# Main.net
KiCad netlist of a schematic drawn in Altium Designer
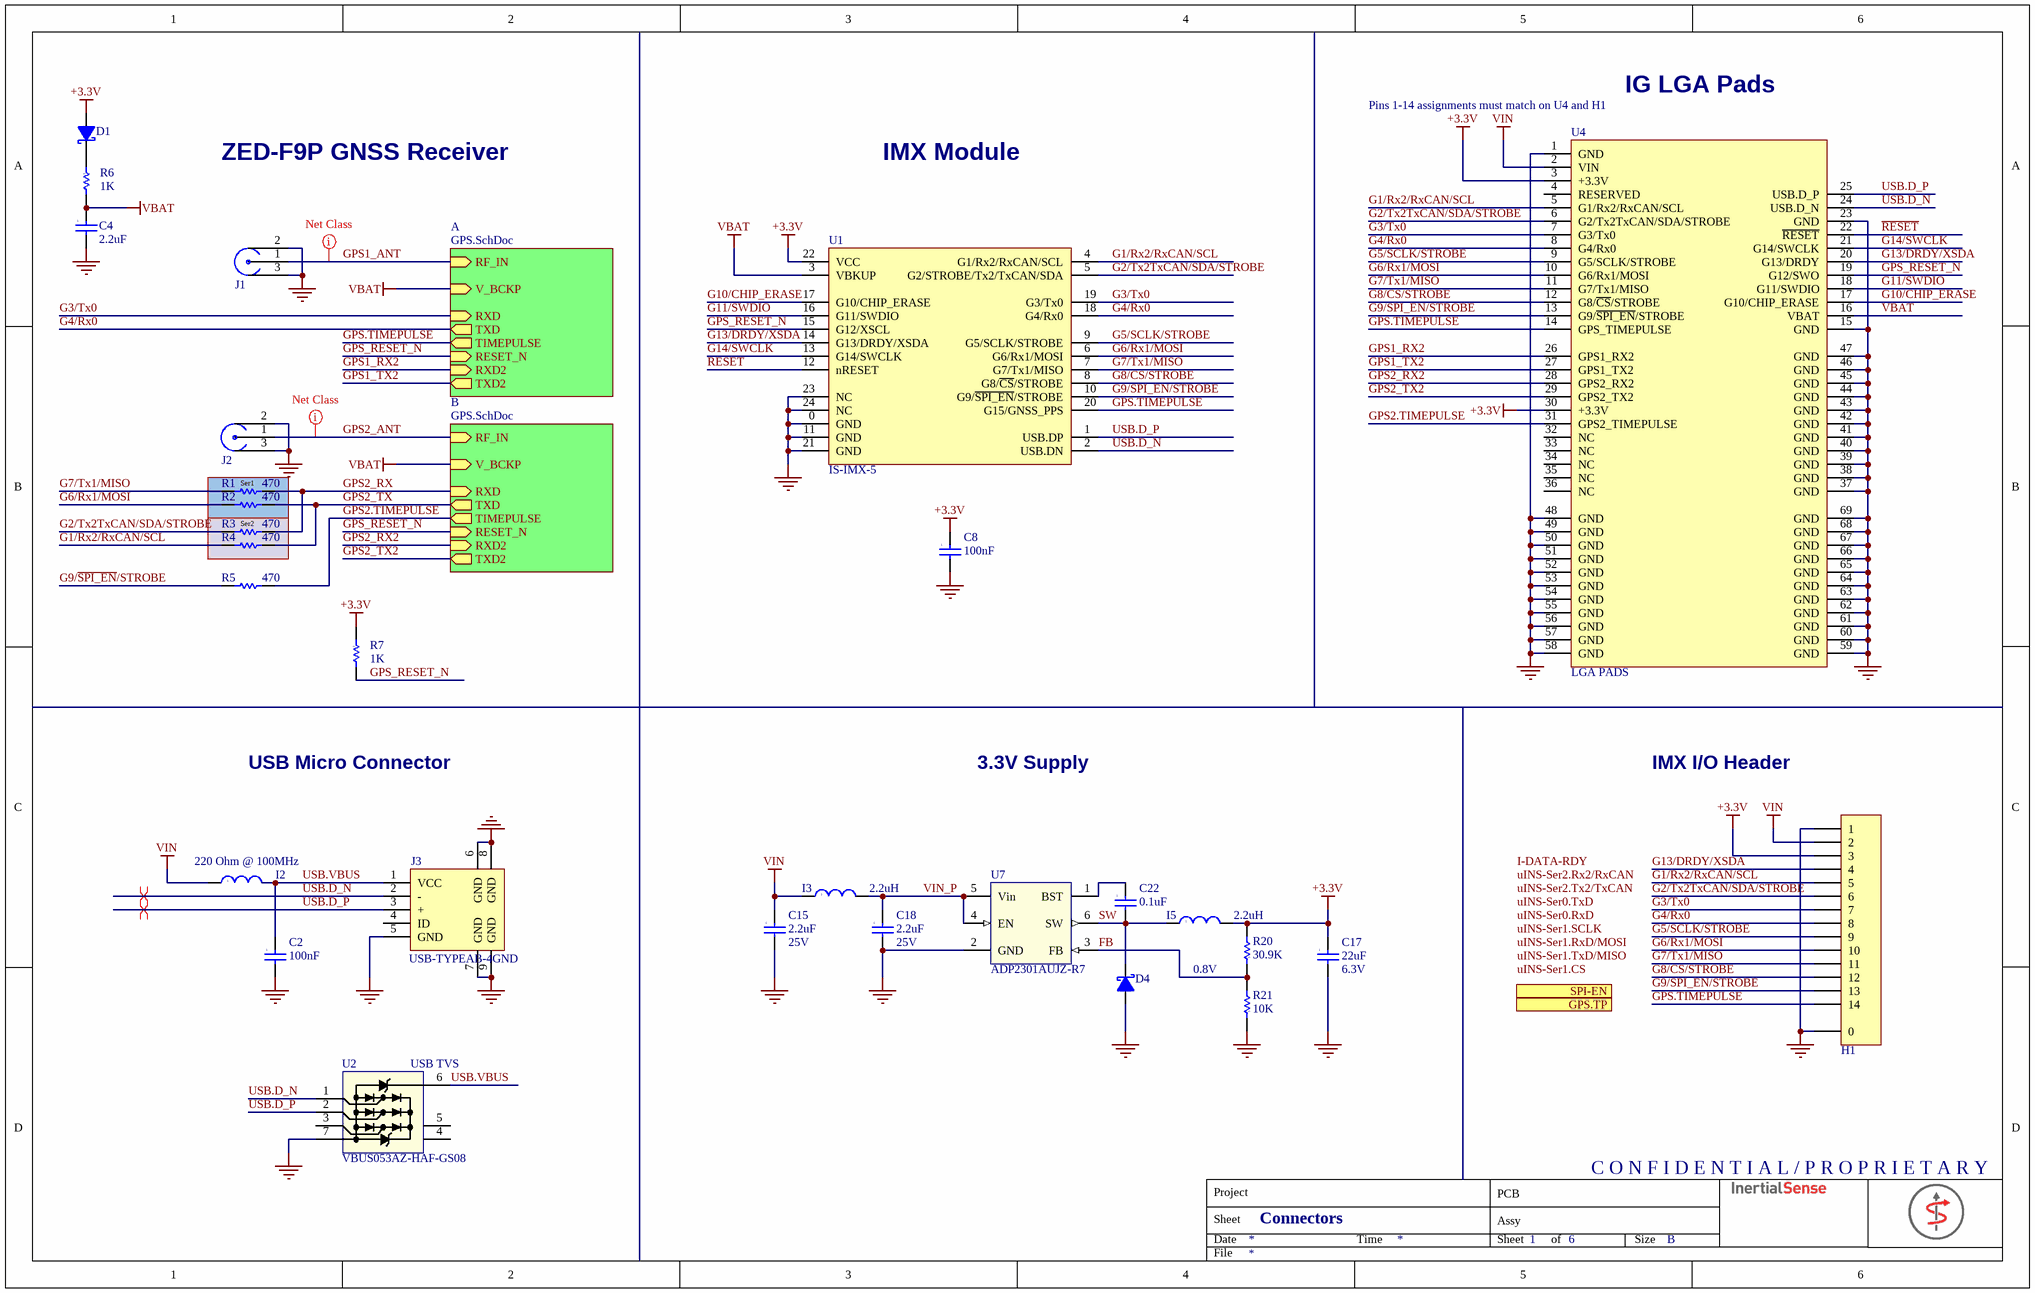
[diagram p0: Main.SchDoc]

(export (version "E")
  (design (tool "Eeschema 10.0.6"))
  (components
    (comp (ref "C2")
      (value "100nF")
      (footprint "0402")
      (description "CAP CER .10UF 50V X7R 10% 0402")
      (fields
        (field (name "MANUFACTURER") "TDK Corporation")
        (field (name "MANUFACTURER PART NUMBER") "C1005X7R1H104K")
        (field (name "PUBLISHER") "Altium Limited")
      )
      (libsource (lib "") (part "Cap_1"))
    )
    (comp (ref "C4")
      (value "2.2uF")
      (footprint "0402")
      (description "0402 2.2 uF 6.3 V ±10% Tolerance X6S Multilayer Ceramic Capacitor")
      (fields
        (field (name "MANUFACTURER") "Murata")
        (field (name "MANUFACTURER PART NUMBER") "GRM155C80J225KE95D")
        (field (name "PUBLISHER") "Altium Limited")
      )
      (libsource (lib "General") (part "Cap"))
    )
    (comp (ref "C8")
      (value "100nF")
      (footprint "0402")
      (description "CAP CER .10UF 50V X7R 10% 0402")
      (fields
        (field (name "MANUFACTURER") "TDK Corporation")
        (field (name "MANUFACTURER PART NUMBER") "C1005X7R1H104K")
        (field (name "PUBLISHER") "Altium Limited")
      )
      (libsource (lib "") (part "Cap_1"))
    )
    (comp (ref "C15")
      (value "2.2uF")
      (footprint "0603")
      (description "CAP CER 2.2UF 25V X6S 0603")
      (fields
        (field (name "MANUFACTURER") "Murata")
        (field (name "MANUFACTURER PART NUMBER") "GRT188C81E225KE13D")
        (field (name "VOLTAGE RATING") "25V")
        (field (name "PUBLISHER") "Altium Limited")
      )
      (libsource (lib "General") (part "Cap"))
    )
    (comp (ref "C17")
      (value "22uF")
      (footprint "0603")
      (description "CAP CER 22UF 6.3V X6S 0603")
      (fields
        (field (name "MANUFACTURER") "Murata")
        (field (name "MANUFACTURER PART NUMBER") "GRM188C80J226ME15D")
        (field (name "VOLTAGE RATING") "6.3V")
        (field (name "PUBLISHER") "Altium Limited")
      )
      (libsource (lib "General") (part "Cap"))
    )
    (comp (ref "C18")
      (value "2.2uF")
      (footprint "0603")
      (description "CAP CER 2.2UF 25V X6S 0603")
      (fields
        (field (name "MANUFACTURER") "Murata")
        (field (name "MANUFACTURER PART NUMBER") "GRT188C81E225KE13D")
        (field (name "VOLTAGE RATING") "25V")
        (field (name "PUBLISHER") "Altium Limited")
      )
      (libsource (lib "General") (part "Cap"))
    )
    (comp (ref "C22")
      (value "0.1uF")
      (footprint "0402")
      (description "CAP CER 0.1UF 50V X7R 0402")
      (fields
        (field (name "MANUFACTURER") "TDK")
        (field (name "MANUFACTURER PART NUMBER") "CGA2B3X7R1H104K050BB")
        (field (name "PUBLISHER") "Altium Limited")
      )
      (libsource (lib "General") (part "Cap"))
    )
    (comp (ref "D1")
      (value "Diode - Schottky")
      (footprint "D0603B")
      (description "DIODE SCHOTTKY 30V 2A 0603")
      (fields
        (field (name "MANUFACTURER") "Vishay")
        (field (name "MANUFACTURER PART NUMBER") "VSKY20301608-G4-08")
      )
      (libsource (lib "General") (part "Diode - Schottky"))
    )
    (comp (ref "D4")
      (value "Diode - Schottky")
      (footprint "D0603B")
      (description "DIODE SCHOTTKY 30V 2A 0603")
      (fields
        (field (name "MANUFACTURER") "Vishay")
        (field (name "MANUFACTURER PART NUMBER") "VSKY20301608-G4-08")
      )
      (libsource (lib "General") (part "Diode - Schottky"))
    )
    (comp (ref "H1")
      (value "Hdr - 14pin - mount")
      (footprint "SM14B-GHS-TB(LF)(SN)")
      (description "Conn Shrouded Header HDR 14 POS 1.25mm Solder ST Top Entry SMD T/R")
      (fields
        (field (name "MANUFACTURER") "JST")
        (field (name "MANUFACTURER PART NUMBER") "SM14B-GHS-TB(LF)(SN)")
      )
      (libsource (lib "Connectors") (part "Hdr - 14pin - mount"))
    )
    (comp (ref "I2")
      (value "220 Ohm @ 100MHz")
      (footprint "I0603")
      (description "FERRITE CHIP 220 OHM 2500MA 0603")
      (fields
        (field (name "MANUFACTURER") "Murata Electronics North America")
        (field (name "MANUFACTURER PART NUMBER") "BLM18SG221TN1D")
      )
      (libsource (lib "") (part "Inductor_1"))
    )
    (comp (ref "I3")
      (value "2.2uH")
      (footprint "0806")
      (description "FIXED IND 2.2UH 1.2A 110 MOHM")
      (fields
        (field (name "MANUFACTURER") "TDK")
        (field (name "MANUFACTURER PART NUMBER") "MLP2016H2R2MT0S1")
      )
      (libsource (lib "General") (part "Inductor"))
    )
    (comp (ref "I5")
      (value "2.2uH")
      (footprint "0806")
      (description "FIXED IND 2.2UH 1.2A 110 MOHM")
      (fields
        (field (name "MANUFACTURER") "TDK")
        (field (name "MANUFACTURER PART NUMBER") "MLP2016H2R2MT0S1")
      )
      (libsource (lib "General") (part "Inductor"))
    )
    (comp (ref "J1")
      (value "RF - GND x 2")
      (footprint "RF UMC SMD")
      (description "CONN UMC RCPT STR 50 OHM SMD")
      (fields
        (field (name "MANUFACTURER") "Emerson Network Power Connectivity Johnson")
        (field (name "MANUFACTURER PART NUMBER") "128-0711-201")
      )
      (libsource (lib "Connectors") (part "RF - GND x 2"))
    )
    (comp (ref "J2")
      (value "RF - GND x 2")
      (footprint "RF UMC SMD")
      (description "CONN UMC RCPT STR 50 OHM SMD")
      (fields
        (field (name "MANUFACTURER") "Emerson Network Power Connectivity Johnson")
        (field (name "MANUFACTURER PART NUMBER") "128-0711-201")
      )
      (libsource (lib "Connectors") (part "RF - GND x 2"))
    )
    (comp (ref "J3")
      (value "USB-TYPEAB-4GND")
      (footprint "USB Micro AB R/A THR")
      (description "CONN USB AB 4POS")
      (fields
        (field (name "MANUFACTURER") "Amphenol FCI")
        (field (name "MANUFACTURER PART NUMBER") "10118194-0001LF")
      )
      (libsource (lib "Connectors") (part "USB-TYPEAB-4GND"))
    )
    (comp (ref "R1")
      (value "470")
      (footprint "R0402")
      (description "RES 470 OHM 1/16W 1% 0402 SMD")
      (fields
        (field (name "MANUFACTURER") "Vishay Dale")
        (field (name "MANUFACTURER PART NUMBER") "CRCW0402470RFKED")
      )
      (libsource (lib "General") (part "Res"))
    )
    (comp (ref "R2")
      (value "470")
      (footprint "R0402")
      (description "RES 470 OHM 1/16W 1% 0402 SMD")
      (fields
        (field (name "MANUFACTURER") "Vishay Dale")
        (field (name "MANUFACTURER PART NUMBER") "CRCW0402470RFKED")
      )
      (libsource (lib "General") (part "Res"))
    )
    (comp (ref "R3")
      (value "470")
      (footprint "R0402")
      (description "RES 470 OHM 1/16W 1% 0402 SMD")
      (fields
        (field (name "MANUFACTURER") "Vishay Dale")
        (field (name "MANUFACTURER PART NUMBER") "CRCW0402470RFKED")
      )
      (libsource (lib "General") (part "Res"))
    )
    (comp (ref "R4")
      (value "470")
      (footprint "R0402")
      (description "RES 470 OHM 1/16W 1% 0402 SMD")
      (fields
        (field (name "MANUFACTURER") "Vishay Dale")
        (field (name "MANUFACTURER PART NUMBER") "CRCW0402470RFKED")
      )
      (libsource (lib "General") (part "Res"))
    )
    (comp (ref "R5")
      (value "470")
      (footprint "R0402")
      (description "RES 470 OHM 1/16W 1% 0402 SMD")
      (fields
        (field (name "MANUFACTURER") "Vishay Dale")
        (field (name "MANUFACTURER PART NUMBER") "CRCW0402470RFKED")
      )
      (libsource (lib "General") (part "Res"))
    )
    (comp (ref "R6")
      (value "1K")
      (footprint "R0402")
      (description "1 kOhms ±1% 0.063W, 1/16W Chip Resistor 0402 (1005 Metric) Moisture Resistant Thick Film")
      (fields
        (field (name "MANUFACTURER") "Yageo")
        (field (name "MANUFACTURER PART NUMBER") "RC0402FR-071KL")
      )
      (libsource (lib "") (part "Res_1"))
    )
    (comp (ref "R7")
      (value "1K")
      (footprint "R0402")
      (description "1 kOhms ±1% 0.063W, 1/16W Chip Resistor 0402 (1005 Metric) Moisture Resistant Thick Film")
      (fields
        (field (name "MANUFACTURER") "Yageo")
        (field (name "MANUFACTURER PART NUMBER") "RC0402FR-071KL")
      )
      (libsource (lib "") (part "Res_1"))
    )
    (comp (ref "R20")
      (value "30.9K")
      (footprint "R0402")
      (description "RES TF 30.9K OHM 1% 1/16W 0402")
      (fields
        (field (name "MANUFACTURER") "Stackpole Electronics Inc")
        (field (name "MANUFACTURER PART NUMBER") "RMCF0402FT30K9")
      )
      (libsource (lib "") (part "Res_2"))
    )
    (comp (ref "R21")
      (value "10K")
      (footprint "R0402")
      (description "RES 10.0K OHM 1/16W 1% 0402 SMD")
      (fields
        (field (name "MANUFACTURER") "Yageo")
        (field (name "MANUFACTURER PART NUMBER") "RC0402FR-0710KL")
      )
      (libsource (lib "") (part "Res_2"))
    )
    (comp (ref "U1")
      (value "IMX")
      (footprint "IS-IMX-5.0")
      (description "Inertial Sense IMX")
      (fields
        (field (name "MANUFACTURER") "Inertial Sense")
        (field (name "MANUFACTURER PART NUMBER") "IS-IMX-5")
      )
      (libsource (lib "IS-IMX-5") (part "IS-IMX-5.0"))
    )
    (comp (ref "U2")
      (value "VBUS053")
      (footprint "QFN50P160X160X60-6N")
      (description "ESD SUPPRESS 5.5V 36W 3-Line USB")
      (fields
        (field (name "MANUFACTURER") "Vishay Semiconductors")
        (field (name "MANUFACTURER PART NUMBER") "VBUS053AZ-HAF-GS08")
      )
      (libsource (lib "ICs") (part "VBUS053"))
    )
    (comp (ref "U4")
      (value "LGA PADS")
      (footprint "IG-1.2-G2_LGA")
      (description "IMX multi-frequency RTK-GNSS Module")
      (libsource (lib "Sensors") (part "IG_1.2-G2_LGA"))
    )
    (comp (ref "U7")
      (value "ADP2301")
      (footprint "MO-178-AB")
      (description "IC BUCK ADJ 1.2A 6TSOT")
      (fields
        (field (name "MANUFACTURER") "Analog Devices Inc")
        (field (name "MANUFACTURER PART NUMBER") "ADP2301AUJZ-R7")
      )
      (libsource (lib "ICs") (part "ADP2301"))
    )
  )
  (nets
    (net (code "1") (name "+3.3V") (class "Default")
      (node (ref "C17") (pin "1") (pinfunction "1_1") (pintype "passive"))
      (node (ref "C8") (pin "1") (pinfunction "1_1") (pintype "passive"))
      (node (ref "D1") (pin "A") (pinfunction "A_A") (pintype "passive"))
      (node (ref "H1") (pin "3") (pinfunction "3_3") (pintype "passive"))
      (node (ref "I5") (pin "2") (pinfunction "2_2") (pintype "passive"))
      (node (ref "R20") (pin "2") (pinfunction "2_2") (pintype "passive"))
      (node (ref "R7") (pin "1") (pinfunction "1_1") (pintype "passive"))
      (node (ref "U1") (pin "22") (pinfunction "VCC_22") (pintype "power_in"))
      (node (ref "U4") (pin "3") (pinfunction "+3.3V_3") (pintype "passive"))
      (node (ref "U4") (pin "30") (pinfunction "+3.3V_30") (pintype "passive"))
    )
    (net (code "2") (name "/FB") (class "Default")
      (node (ref "R20") (pin "1") (pinfunction "1_1") (pintype "passive"))
      (node (ref "R21") (pin "2") (pinfunction "2_2") (pintype "passive"))
      (node (ref "U7") (pin "3") (pinfunction "FB_3") (pintype "input"))
    )
    (net (code "3") (name "/G1{slash}Rx2{slash}RxCAN{slash}SCL") (class "Default")
      (node (ref "H1") (pin "5") (pinfunction "5_5") (pintype "passive"))
      (node (ref "R4") (pin "1") (pinfunction "1_1") (pintype "passive"))
      (node (ref "U1") (pin "4") (pinfunction "G1/Rx2/RxCAN/SCL_4") (pintype "passive"))
      (node (ref "U4") (pin "5") (pinfunction "G1/Rx2/RxCAN/SCL_5") (pintype "passive"))
    )
    (net (code "4") (name "/G2{slash}Tx2TxCAN{slash}SDA{slash}STROBE") (class "Default")
      (node (ref "H1") (pin "6") (pinfunction "6_6") (pintype "passive"))
      (node (ref "R3") (pin "1") (pinfunction "1_1") (pintype "passive"))
      (node (ref "U1") (pin "5") (pinfunction "G2/STROBE/Tx2/TxCAN/SDA_5") (pintype "passive"))
      (node (ref "U4") (pin "6") (pinfunction "G2/Tx2TxCAN/SDA/STROBE_6") (pintype "passive"))
    )
    (net (code "5") (name "/G3{slash}Tx0") (class "Default")
      (node (ref "H1") (pin "7") (pinfunction "7_7") (pintype "passive"))
      (node (ref "U1") (pin "19") (pinfunction "G3/Tx0_19") (pintype "passive"))
      (node (ref "U4") (pin "7") (pinfunction "G3/Tx0_7") (pintype "passive"))
    )
    (net (code "6") (name "/G4{slash}Rx0") (class "Default")
      (node (ref "H1") (pin "8") (pinfunction "8_8") (pintype "passive"))
      (node (ref "U1") (pin "18") (pinfunction "G4/Rx0_18") (pintype "passive"))
      (node (ref "U4") (pin "8") (pinfunction "G4/Rx0_8") (pintype "passive"))
    )
    (net (code "7") (name "/G5{slash}SCLK{slash}STROBE") (class "Default")
      (node (ref "H1") (pin "9") (pinfunction "9_9") (pintype "passive"))
      (node (ref "U1") (pin "9") (pinfunction "G5/SCLK/STROBE_9") (pintype "passive"))
      (node (ref "U4") (pin "9") (pinfunction "G5/SCLK/STROBE_9") (pintype "passive"))
    )
    (net (code "8") (name "/G6{slash}Rx1{slash}MOSI") (class "Default")
      (node (ref "H1") (pin "10") (pinfunction "10_10") (pintype "passive"))
      (node (ref "R2") (pin "1") (pinfunction "1_1") (pintype "passive"))
      (node (ref "U1") (pin "6") (pinfunction "G6/Rx1/MOSI_6") (pintype "passive"))
      (node (ref "U4") (pin "10") (pinfunction "G6/Rx1/MOSI_10") (pintype "passive"))
    )
    (net (code "9") (name "/G7{slash}Tx1{slash}MISO") (class "Default")
      (node (ref "H1") (pin "11") (pinfunction "11_11") (pintype "passive"))
      (node (ref "R1") (pin "1") (pinfunction "1_1") (pintype "passive"))
      (node (ref "U1") (pin "7") (pinfunction "G7/Tx1/MISO_7") (pintype "passive"))
      (node (ref "U4") (pin "11") (pinfunction "G7/Tx1/MISO_11") (pintype "passive"))
    )
    (net (code "10") (name "/G8{slash}~{CS}{slash}STROBE") (class "Default")
      (node (ref "H1") (pin "12") (pinfunction "12_12") (pintype "passive"))
      (node (ref "U1") (pin "8") (pinfunction "G8/~{CS}/STROBE_8") (pintype "passive"))
      (node (ref "U4") (pin "12") (pinfunction "G8/~{CS}/STROBE_12") (pintype "passive"))
    )
    (net (code "11") (name "/G9{slash}~{SPI_EN}{slash}STROBE") (class "Default")
      (node (ref "H1") (pin "13") (pinfunction "13_13") (pintype "passive"))
      (node (ref "R5") (pin "1") (pinfunction "1_1") (pintype "passive"))
      (node (ref "U1") (pin "10") (pinfunction "G9/~{SPI_EN}/STROBE_10") (pintype "passive"))
      (node (ref "U4") (pin "13") (pinfunction "G9/~{SPI_EN}/STROBE_13") (pintype "passive"))
    )
    (net (code "12") (name "/G10{slash}CHIP_ERASE") (class "Default")
      (node (ref "U1") (pin "17") (pinfunction "G10/CHIP_ERASE_17") (pintype "passive"))
      (node (ref "U4") (pin "17") (pinfunction "G10/CHIP_ERASE_17") (pintype "passive"))
    )
    (net (code "13") (name "/G11{slash}SWDIO") (class "Default")
      (node (ref "U1") (pin "16") (pinfunction "G11/SWDIO_16") (pintype "passive"))
      (node (ref "U4") (pin "18") (pinfunction "G11/SWDIO_18") (pintype "passive"))
    )
    (net (code "14") (name "/G13{slash}DRDY{slash}XSDA") (class "Default")
      (node (ref "H1") (pin "4") (pinfunction "4_4") (pintype "passive"))
      (node (ref "U1") (pin "14") (pinfunction "G13/DRDY/XSDA_14") (pintype "passive"))
      (node (ref "U4") (pin "20") (pinfunction "G13/DRDY_20") (pintype "passive"))
    )
    (net (code "15") (name "/G14{slash}SWCLK") (class "Default")
      (node (ref "U1") (pin "13") (pinfunction "G14/SWCLK_13") (pintype "passive"))
      (node (ref "U4") (pin "21") (pinfunction "G14/SWCLK_21") (pintype "passive"))
    )
    (net (code "16") (name "/GPS.TIMEPULSE") (class "Default")
      (node (ref "H1") (pin "14") (pinfunction "14_14") (pintype "passive"))
      (node (ref "U1") (pin "20") (pinfunction "G15/GNSS_PPS_20") (pintype "passive"))
      (node (ref "U4") (pin "14") (pinfunction "GPS_TIMEPULSE_14") (pintype "passive"))
    )
    (net (code "18") (name "/GPS1_ANT") (class "Default")
      (node (ref "J1") (pin "1") (pinfunction "1_1") (pintype "passive"))
    )
    (net (code "19") (name "/GPS1_RX2") (class "Default")
      (node (ref "U4") (pin "26") (pinfunction "GPS1_RX2_26") (pintype "passive"))
    )
    (net (code "20") (name "/GPS1_TX2") (class "Default")
      (node (ref "U4") (pin "27") (pinfunction "GPS1_TX2_27") (pintype "passive"))
    )
    (net (code "21") (name "/GPS2.TIMEPULSE") (class "Default")
      (node (ref "R5") (pin "2") (pinfunction "2_2") (pintype "passive"))
      (node (ref "U4") (pin "31") (pinfunction "GPS2_TIMEPULSE_31") (pintype "passive"))
    )
    (net (code "22") (name "/GPS2_ANT") (class "Default")
      (node (ref "J2") (pin "1") (pinfunction "1_1") (pintype "passive"))
    )
    (net (code "23") (name "/GPS2_RX") (class "Default")
      (node (ref "R1") (pin "2") (pinfunction "2_2") (pintype "passive"))
      (node (ref "R3") (pin "2") (pinfunction "2_2") (pintype "passive"))
    )
    (net (code "24") (name "/GPS2_RX2") (class "Default")
      (node (ref "U4") (pin "28") (pinfunction "GPS2_RX2_28") (pintype "passive"))
    )
    (net (code "25") (name "/GPS2_TX") (class "Default")
      (node (ref "R2") (pin "2") (pinfunction "2_2") (pintype "passive"))
      (node (ref "R4") (pin "2") (pinfunction "2_2") (pintype "passive"))
    )
    (net (code "26") (name "/GPS2_TX2") (class "Default")
      (node (ref "U4") (pin "29") (pinfunction "GPS2_TX2_29") (pintype "passive"))
    )
    (net (code "27") (name "/GPS_RESET_N") (class "Default")
      (node (ref "R7") (pin "2") (pinfunction "2_2") (pintype "passive"))
      (node (ref "U1") (pin "15") (pinfunction "G12/XSCL_15") (pintype "passive"))
      (node (ref "U4") (pin "19") (pinfunction "G12/SWO_19") (pintype "passive"))
    )
    (net (code "29") (name "/RESET") (class "Default")
      (node (ref "U1") (pin "12") (pinfunction "nRESET_12") (pintype "passive"))
      (node (ref "U4") (pin "22") (pinfunction "~{RESET}_22") (pintype "passive"))
    )
    (net (code "31") (name "/SW") (class "Default")
      (node (ref "C22") (pin "2") (pinfunction "2_2") (pintype "passive"))
      (node (ref "D4") (pin "C") (pinfunction "C_C") (pintype "passive"))
      (node (ref "I5") (pin "1") (pinfunction "1_1") (pintype "passive"))
      (node (ref "U7") (pin "6") (pinfunction "SW_6") (pintype "output"))
    )
    (net (code "32") (name "/USB.D_N") (class "Default")
      (node (ref "J3") (pin "2") (pinfunction "-_2") (pintype "passive"))
      (node (ref "U1") (pin "2") (pinfunction "USB.DN_2") (pintype "passive"))
      (node (ref "U2") (pin "1") (pintype "passive"))
      (node (ref "U4") (pin "24") (pinfunction "USB.D_N_24") (pintype "passive"))
    )
    (net (code "33") (name "/USB.D_P") (class "Default")
      (node (ref "J3") (pin "3") (pinfunction "+_3") (pintype "passive"))
      (node (ref "U1") (pin "1") (pinfunction "USB.DP_1") (pintype "passive"))
      (node (ref "U2") (pin "2") (pintype "passive"))
      (node (ref "U4") (pin "25") (pinfunction "USB.D_P_25") (pintype "passive"))
    )
    (net (code "34") (name "/USB.VBUS") (class "Default")
      (node (ref "C2") (pin "1") (pinfunction "1_1") (pintype "passive"))
      (node (ref "I2") (pin "2") (pinfunction "2_2") (pintype "passive"))
      (node (ref "J3") (pin "1") (pinfunction "VCC_1") (pintype "passive"))
      (node (ref "U2") (pin "6") (pintype "passive"))
    )
    (net (code "35") (name "/VIN_P") (class "Default")
      (node (ref "C18") (pin "1") (pinfunction "1_1") (pintype "passive"))
      (node (ref "I3") (pin "2") (pinfunction "2_2") (pintype "passive"))
      (node (ref "U7") (pin "4") (pinfunction "EN_4") (pintype "input"))
      (node (ref "U7") (pin "5") (pinfunction "Vin_5") (pintype "power_in"))
    )
    (net (code "44") (name "GND") (class "Default")
      (node (ref "C15") (pin "2") (pinfunction "2_2") (pintype "passive"))
      (node (ref "C17") (pin "2") (pinfunction "2_2") (pintype "passive"))
      (node (ref "C18") (pin "2") (pinfunction "2_2") (pintype "passive"))
      (node (ref "C2") (pin "2") (pinfunction "2_2") (pintype "passive"))
      (node (ref "C4") (pin "2") (pinfunction "2_2") (pintype "passive"))
      (node (ref "C8") (pin "2") (pinfunction "2_2") (pintype "passive"))
      (node (ref "D4") (pin "A") (pinfunction "A_A") (pintype "passive"))
      (node (ref "H1") (pin "0") (pinfunction "0_0") (pintype "passive"))
      (node (ref "H1") (pin "1") (pinfunction "1_1") (pintype "passive"))
      (node (ref "J1") (pin "2") (pinfunction "2_2") (pintype "passive"))
      (node (ref "J1") (pin "3") (pinfunction "3_3") (pintype "passive"))
      (node (ref "J2") (pin "2") (pinfunction "2_2") (pintype "passive"))
      (node (ref "J2") (pin "3") (pinfunction "3_3") (pintype "passive"))
      (node (ref "J3") (pin "5") (pinfunction "GND_5") (pintype "passive"))
      (node (ref "J3") (pin "6") (pinfunction "GND_6") (pintype "passive"))
      (node (ref "J3") (pin "7") (pinfunction "GND_7") (pintype "passive"))
      (node (ref "J3") (pin "8") (pinfunction "GND_8") (pintype "passive"))
      (node (ref "J3") (pin "9") (pinfunction "GND_9") (pintype "passive"))
      (node (ref "R21") (pin "1") (pinfunction "1_1") (pintype "passive"))
      (node (ref "U1") (pin "0") (pinfunction "GND_0") (pintype "power_in"))
      (node (ref "U1") (pin "11") (pinfunction "GND_11") (pintype "power_in"))
      (node (ref "U1") (pin "21") (pinfunction "GND_21") (pintype "power_in"))
      (node (ref "U1") (pin "23") (pinfunction "NC_23") (pintype "power_in"))
      (node (ref "U1") (pin "24") (pinfunction "NC_24") (pintype "power_in"))
      (node (ref "U2") (pin "7") (pintype "passive"))
      (node (ref "U4") (pin "1") (pinfunction "GND_1") (pintype "passive"))
      (node (ref "U4") (pin "15") (pinfunction "GND_15") (pintype "passive"))
      (node (ref "U4") (pin "23") (pinfunction "GND_23") (pintype "passive"))
      (node (ref "U4") (pin "37") (pinfunction "GND_37") (pintype "passive"))
      (node (ref "U4") (pin "38") (pinfunction "GND_38") (pintype "passive"))
      (node (ref "U4") (pin "39") (pinfunction "GND_39") (pintype "passive"))
      (node (ref "U4") (pin "40") (pinfunction "GND_40") (pintype "passive"))
      (node (ref "U4") (pin "41") (pinfunction "GND_41") (pintype "passive"))
      (node (ref "U4") (pin "42") (pinfunction "GND_42") (pintype "passive"))
      (node (ref "U4") (pin "43") (pinfunction "GND_43") (pintype "passive"))
      (node (ref "U4") (pin "44") (pinfunction "GND_44") (pintype "passive"))
      (node (ref "U4") (pin "45") (pinfunction "GND_45") (pintype "passive"))
      (node (ref "U4") (pin "46") (pinfunction "GND_46") (pintype "passive"))
      (node (ref "U4") (pin "47") (pinfunction "GND_47") (pintype "passive"))
      (node (ref "U4") (pin "48") (pinfunction "GND_48") (pintype "passive"))
      (node (ref "U4") (pin "49") (pinfunction "GND_49") (pintype "passive"))
      (node (ref "U4") (pin "50") (pinfunction "GND_50") (pintype "passive"))
      (node (ref "U4") (pin "51") (pinfunction "GND_51") (pintype "passive"))
      (node (ref "U4") (pin "52") (pinfunction "GND_52") (pintype "passive"))
      (node (ref "U4") (pin "53") (pinfunction "GND_53") (pintype "passive"))
      (node (ref "U4") (pin "54") (pinfunction "GND_54") (pintype "passive"))
      (node (ref "U4") (pin "55") (pinfunction "GND_55") (pintype "passive"))
      (node (ref "U4") (pin "56") (pinfunction "GND_56") (pintype "passive"))
      (node (ref "U4") (pin "57") (pinfunction "GND_57") (pintype "passive"))
      (node (ref "U4") (pin "58") (pinfunction "GND_58") (pintype "passive"))
      (node (ref "U4") (pin "59") (pinfunction "GND_59") (pintype "passive"))
      (node (ref "U4") (pin "60") (pinfunction "GND_60") (pintype "passive"))
      (node (ref "U4") (pin "61") (pinfunction "GND_61") (pintype "passive"))
      (node (ref "U4") (pin "62") (pinfunction "GND_62") (pintype "passive"))
      (node (ref "U4") (pin "63") (pinfunction "GND_63") (pintype "passive"))
      (node (ref "U4") (pin "64") (pinfunction "GND_64") (pintype "passive"))
      (node (ref "U4") (pin "65") (pinfunction "GND_65") (pintype "passive"))
      (node (ref "U4") (pin "66") (pinfunction "GND_66") (pintype "passive"))
      (node (ref "U4") (pin "67") (pinfunction "GND_67") (pintype "passive"))
      (node (ref "U4") (pin "68") (pinfunction "GND_68") (pintype "passive"))
      (node (ref "U4") (pin "69") (pinfunction "GND_69") (pintype "passive"))
      (node (ref "U7") (pin "2") (pinfunction "GND_2") (pintype "power_in"))
    )
    (net (code "45") (name "Net-(D1-PadC)") (class "Default")
      (node (ref "D1") (pin "C") (pinfunction "C_C") (pintype "passive"))
      (node (ref "R6") (pin "1") (pinfunction "1_1") (pintype "passive"))
    )
    (net (code "46") (name "Net-(U7-BST)") (class "Default")
      (node (ref "C22") (pin "1") (pinfunction "1_1") (pintype "passive"))
      (node (ref "U7") (pin "1") (pinfunction "BST_1") (pintype "passive"))
    )
    (net (code "47") (name "VBAT") (class "Default")
      (node (ref "C4") (pin "1") (pinfunction "1_1") (pintype "passive"))
      (node (ref "R6") (pin "2") (pinfunction "2_2") (pintype "passive"))
      (node (ref "U1") (pin "3") (pinfunction "VBKUP_3") (pintype "passive"))
      (node (ref "U4") (pin "16") (pinfunction "VBAT_16") (pintype "passive"))
    )
    (net (code "48") (name "VIN") (class "Default")
      (node (ref "C15") (pin "1") (pinfunction "1_1") (pintype "passive"))
      (node (ref "H1") (pin "2") (pinfunction "2_2") (pintype "passive"))
      (node (ref "I2") (pin "1") (pinfunction "1_1") (pintype "passive"))
      (node (ref "I3") (pin "1") (pinfunction "1_1") (pintype "passive"))
      (node (ref "U4") (pin "2") (pinfunction "VIN_2") (pintype "passive"))
    )
    (net (code "49") (name "unconnected-(J3-ID-Pad4)") (class "Default")
      (node (ref "J3") (pin "4") (pinfunction "ID_4") (pintype "passive"))
    )
    (net (code "50") (name "unconnected-(U2-Pad3)") (class "Default")
      (node (ref "U2") (pin "3") (pintype "passive"))
    )
    (net (code "51") (name "unconnected-(U2-nc-Pad4)") (class "Default")
      (node (ref "U2") (pin "4") (pinfunction "nc_4") (pintype "passive"))
    )
    (net (code "52") (name "unconnected-(U2-nc-Pad5)") (class "Default")
      (node (ref "U2") (pin "5") (pinfunction "nc_5") (pintype "passive"))
    )
    (net (code "53") (name "unconnected-(U4-NC-Pad32)") (class "Default")
      (node (ref "U4") (pin "32") (pinfunction "NC_32") (pintype "passive"))
    )
    (net (code "54") (name "unconnected-(U4-NC-Pad33)") (class "Default")
      (node (ref "U4") (pin "33") (pinfunction "NC_33") (pintype "passive"))
    )
    (net (code "55") (name "unconnected-(U4-NC-Pad34)") (class "Default")
      (node (ref "U4") (pin "34") (pinfunction "NC_34") (pintype "passive"))
    )
    (net (code "56") (name "unconnected-(U4-NC-Pad35)") (class "Default")
      (node (ref "U4") (pin "35") (pinfunction "NC_35") (pintype "passive"))
    )
    (net (code "57") (name "unconnected-(U4-NC-Pad36)") (class "Default")
      (node (ref "U4") (pin "36") (pinfunction "NC_36") (pintype "passive"))
    )
    (net (code "58") (name "unconnected-(U4-RESERVED-Pad4)") (class "Default")
      (node (ref "U4") (pin "4") (pinfunction "RESERVED_4") (pintype "passive"))
    )
  )
)
